# CKR_BM_v4_2_TR.net
KiCad netlist of a schematic drawn in EAGLE
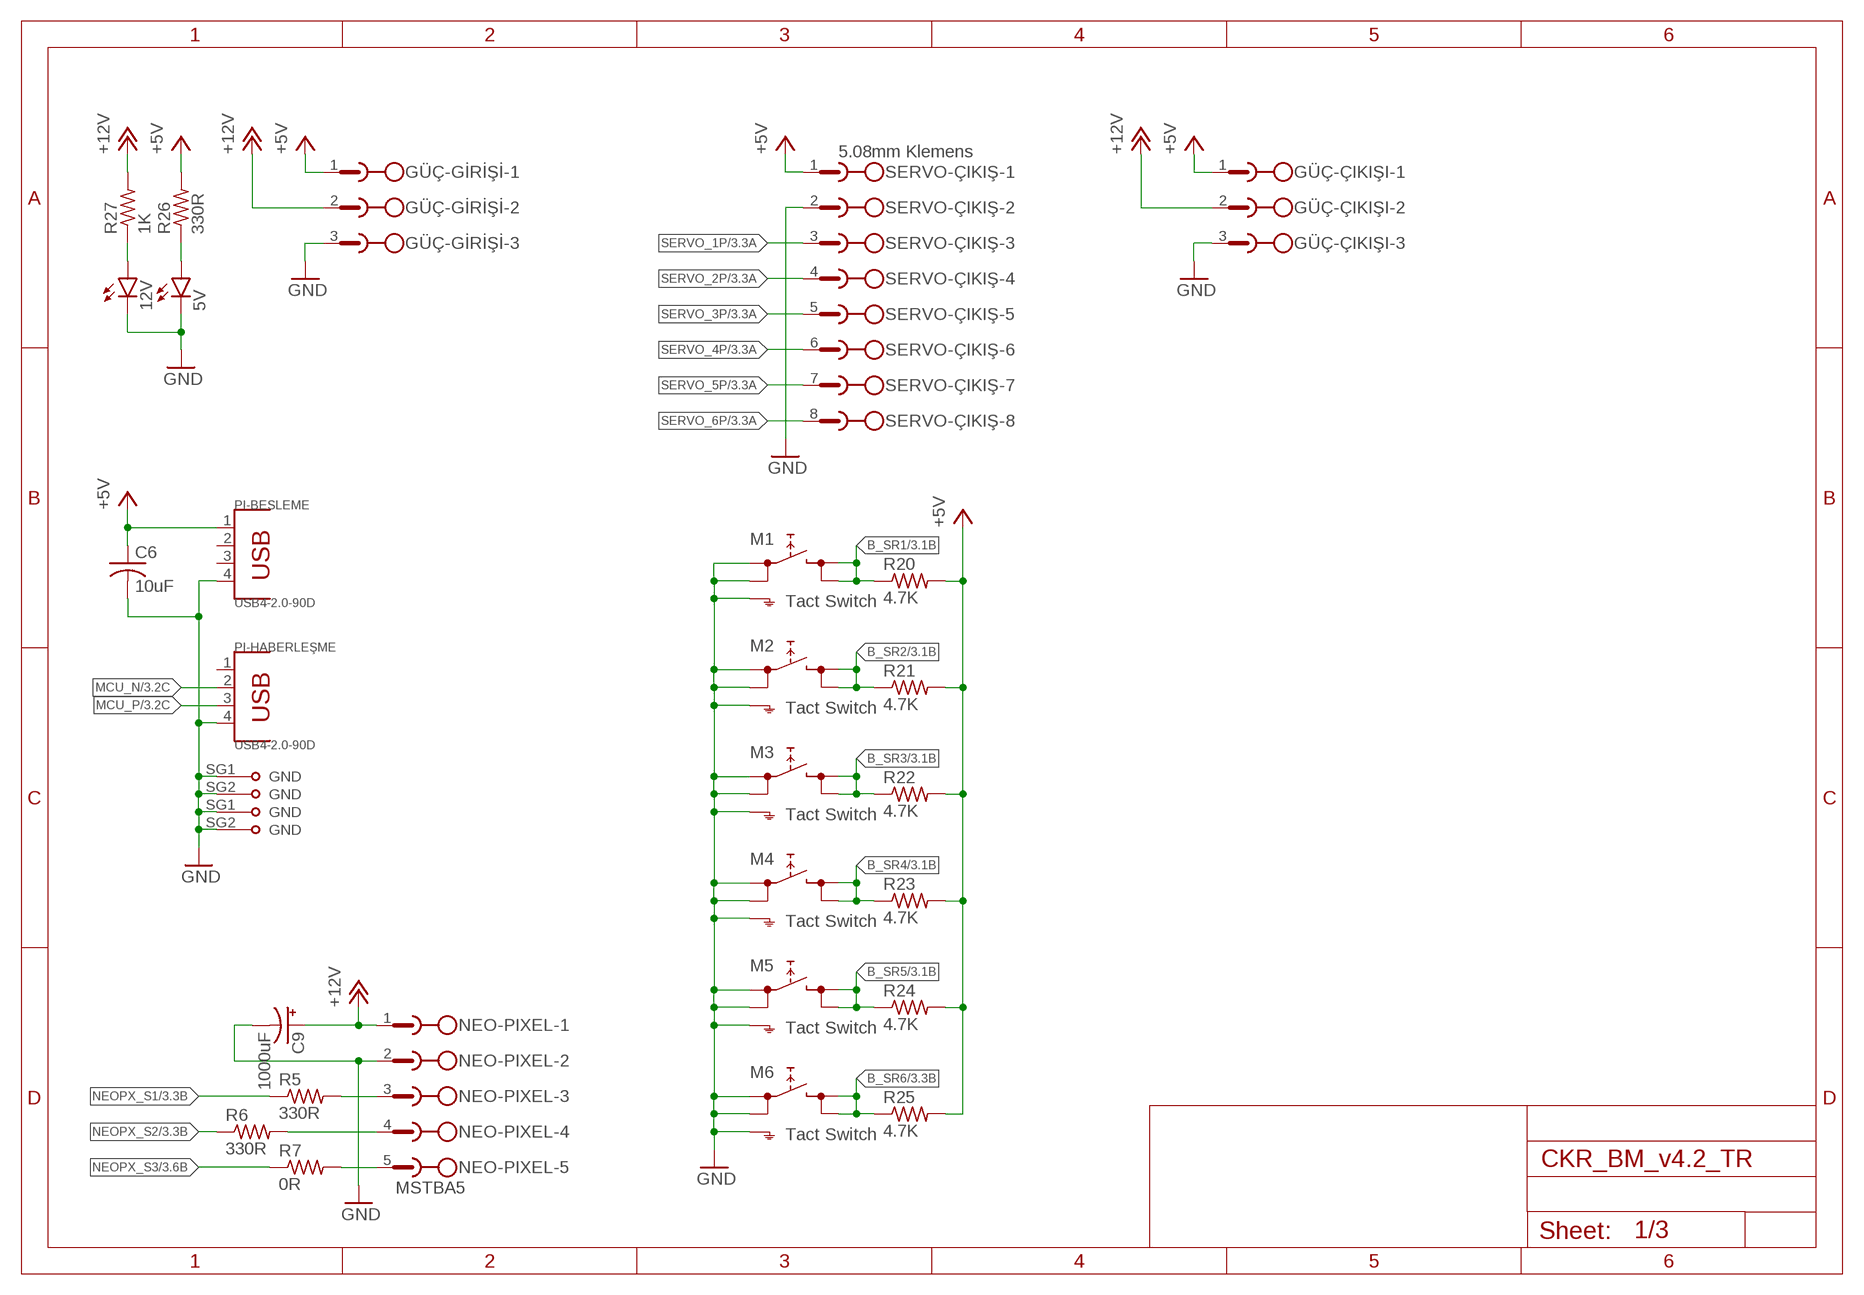
[diagram p0: schematic, sheet 1]
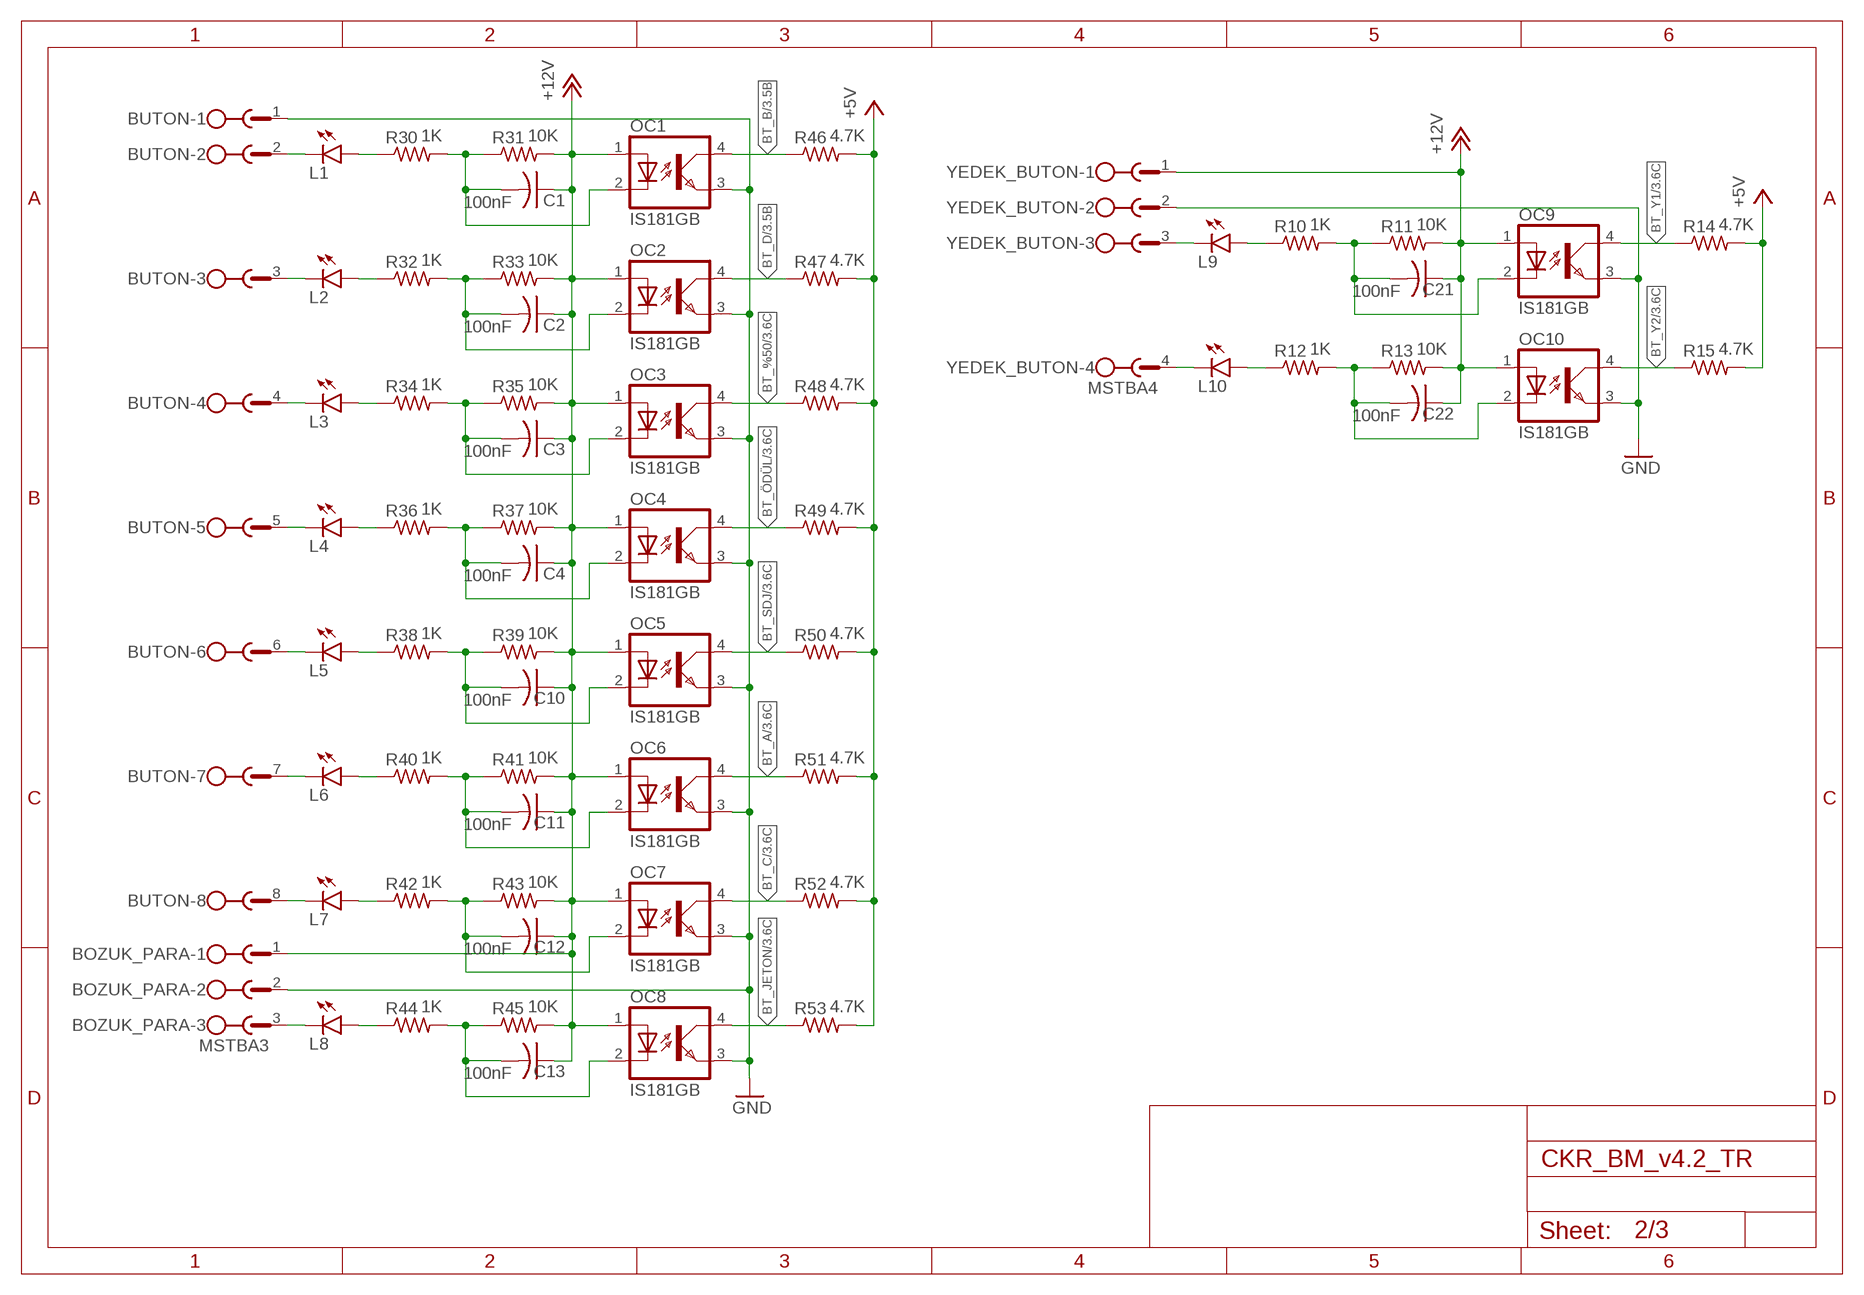
[diagram p1: schematic, sheet 2]
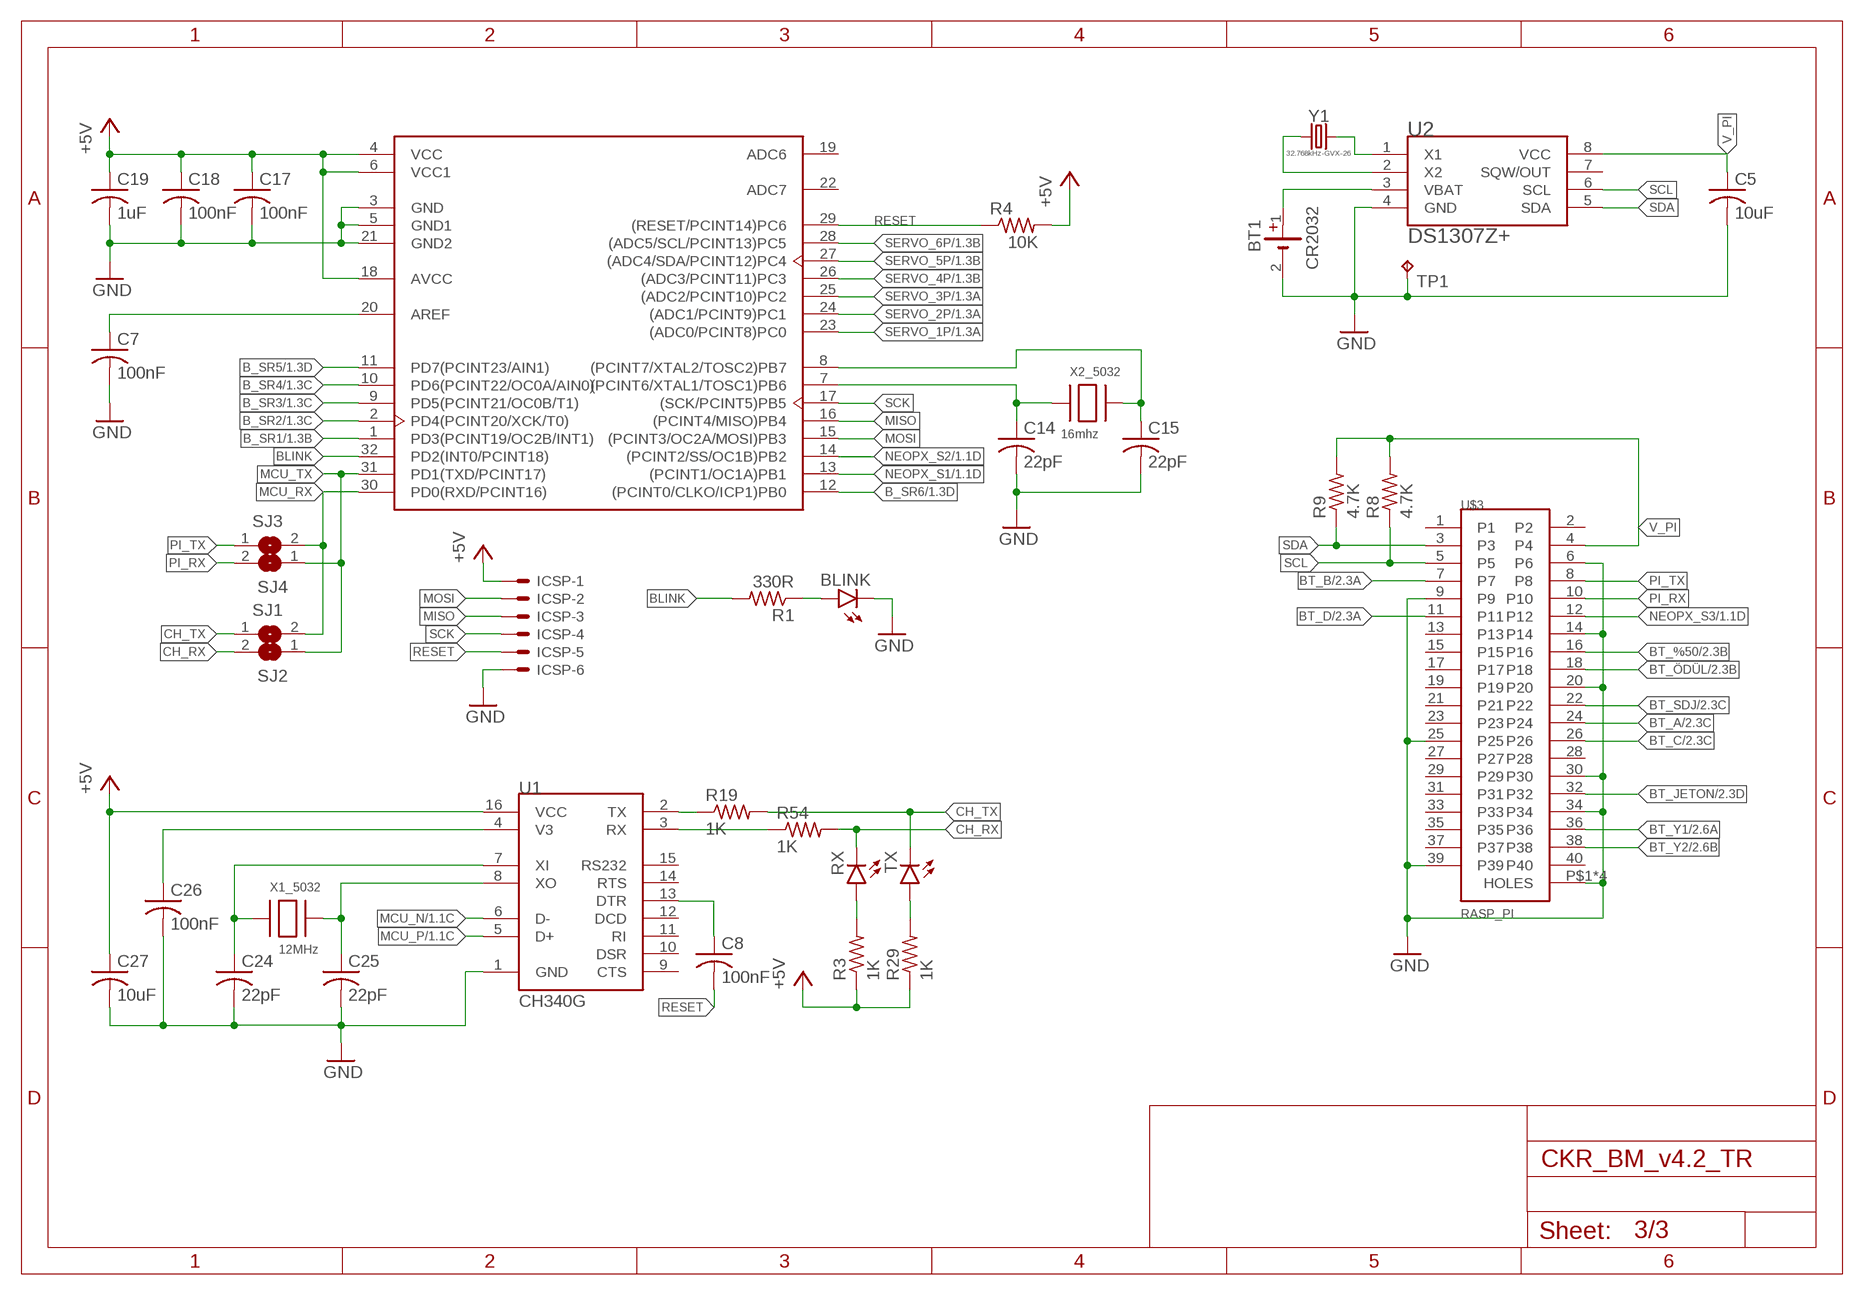
[diagram p2: schematic, sheet 3]

(export (version "E")
  (design (tool "Eeschema 10.0.6"))
  (components
    (comp (ref "BLINK")
      (value "LEDCHIP-LED0805")
      (footprint "eagle-import:CHIP-LED0805")
      (libsource (lib "eagle-import") (part "LEDCHIP-LED0805"))
    )
    (comp (ref "BT1")
      (value "CR2032")
      (footprint "eagle-import:79528211")
      (fields
        (field (name "DIGIKEY_PART_NO") "732-12326-ND")
        (field (name "MANUFACTURER") "Wurth Electronics Inc.")
        (field (name "MPN") "79528211")
        (field (name "CREATED_BY") "PCBLayout.com")
      )
      (libsource (lib "eagle-import") (part "79528211"))
    )
    (comp (ref "C5")
      (value "10uF")
      (footprint "eagle-import:C0805")
      (libsource (lib "eagle-import") (part "C-USC0805"))
    )
    (comp (ref "C7")
      (value "100nF")
      (footprint "eagle-import:C0805")
      (libsource (lib "eagle-import") (part "C-USC0805"))
    )
    (comp (ref "C8")
      (value "100nF")
      (footprint "eagle-import:C0805")
      (libsource (lib "eagle-import") (part "C-USC0805"))
    )
    (comp (ref "C14")
      (value "22pF")
      (footprint "eagle-import:C0805")
      (libsource (lib "eagle-import") (part "C-USC0805"))
    )
    (comp (ref "C15")
      (value "22pF")
      (footprint "eagle-import:C0805")
      (libsource (lib "eagle-import") (part "C-USC0805"))
    )
    (comp (ref "C17")
      (value "100nF")
      (footprint "eagle-import:C0805")
      (libsource (lib "eagle-import") (part "C-USC0805"))
    )
    (comp (ref "C18")
      (value "100nF")
      (footprint "eagle-import:C0805")
      (libsource (lib "eagle-import") (part "C-USC0805"))
    )
    (comp (ref "C19")
      (value "1uF")
      (footprint "eagle-import:C0805")
      (libsource (lib "eagle-import") (part "C-USC0805"))
    )
    (comp (ref "C24")
      (value "22pF")
      (footprint "eagle-import:C0805")
      (libsource (lib "eagle-import") (part "C-USC0805"))
    )
    (comp (ref "C25")
      (value "22pF")
      (footprint "eagle-import:C0805")
      (libsource (lib "eagle-import") (part "C-USC0805"))
    )
    (comp (ref "C26")
      (value "100nF")
      (footprint "eagle-import:C0805")
      (libsource (lib "eagle-import") (part "C-USC0805"))
    )
    (comp (ref "C27")
      (value "10uF")
      (footprint "eagle-import:C0805")
      (libsource (lib "eagle-import") (part "C-USC0805"))
    )
    (comp (ref "ICSP")
      (value "C-GRID-06-70543")
      (footprint "eagle-import:70543-06")
      (fields (field (name "MF") "MOLEX"))
      (libsource (lib "eagle-import") (part "C-GRID-06-70543"))
    )
    (comp (ref "R1")
      (value "330R")
      (footprint "eagle-import:R0805")
      (libsource (lib "eagle-import") (part "R-US_R0805"))
    )
    (comp (ref "R3")
      (value "1K")
      (footprint "eagle-import:R0805")
      (libsource (lib "eagle-import") (part "R-US_R0805"))
    )
    (comp (ref "R4")
      (value "10K")
      (footprint "eagle-import:R0805")
      (libsource (lib "eagle-import") (part "R-US_R0805"))
    )
    (comp (ref "R8")
      (value "4.7K")
      (footprint "eagle-import:R0805")
      (libsource (lib "eagle-import") (part "R-US_R0805"))
    )
    (comp (ref "R9")
      (value "4.7K")
      (footprint "eagle-import:R0805")
      (libsource (lib "eagle-import") (part "R-US_R0805"))
    )
    (comp (ref "R19")
      (value "1K")
      (footprint "eagle-import:R0805")
      (libsource (lib "eagle-import") (part "R-US_R0805"))
    )
    (comp (ref "R29")
      (value "1K")
      (footprint "eagle-import:R0805")
      (libsource (lib "eagle-import") (part "R-US_R0805"))
    )
    (comp (ref "R54")
      (value "1K")
      (footprint "eagle-import:R0805")
      (libsource (lib "eagle-import") (part "R-US_R0805"))
    )
    (comp (ref "RX")
      (value "LEDCHIP-LED0805")
      (footprint "eagle-import:CHIP-LED0805")
      (libsource (lib "eagle-import") (part "LEDCHIP-LED0805"))
    )
    (comp (ref "SJ1") (value "SJ") (footprint "eagle-import:SJ") (libsource (lib "eagle-import") (part "SJ")))
    (comp (ref "SJ2") (value "SJ") (footprint "eagle-import:SJ") (libsource (lib "eagle-import") (part "SJ")))
    (comp (ref "SJ3") (value "SJ") (footprint "eagle-import:SJ") (libsource (lib "eagle-import") (part "SJ")))
    (comp (ref "SJ4") (value "SJ") (footprint "eagle-import:SJ") (libsource (lib "eagle-import") (part "SJ")))
    (comp (ref "TP1")
      (value "GND")
      (footprint "eagle-import:TP15R")
      (libsource (lib "eagle-import") (part "TPTP15R"))
    )
    (comp (ref "TX")
      (value "LEDCHIP-LED0805")
      (footprint "eagle-import:CHIP-LED0805")
      (libsource (lib "eagle-import") (part "LEDCHIP-LED0805"))
    )
    (comp (ref "U$3")
      (value "RASP_PI")
      (footprint "eagle-import:RASP_PI")
      (libsource (lib "eagle-import") (part "RASP_PI"))
    )
    (comp (ref "U1")
      (value "CH340G")
      (footprint "eagle-import:SOIC16")
      (libsource (lib "eagle-import") (part "CH340G"))
    )
    (comp (ref "U2")
      (value "DS1307Z+")
      (footprint "eagle-import:SOIC-8N")
      (fields
        (field (name "DIGI-KEY_PART_NUMBER") "DS1307Z+-ND")
        (field (name "MANUFACTURER") "Maxim Integrated")
        (field (name "CREATED_BY") "PCBLayout.com")
      )
      (libsource (lib "eagle-import") (part "DS1307Z+"))
    )
    (comp (ref "U4")
      (value "ATMEGA328P-AU")
      (footprint "eagle-import:TQFP-32")
      (fields
        (field (name "DIGIKEY_PART_NUMBER") "ATMEGA328P-AU-ND")
        (field (name "MANUFACTURER") "Microchip Technology")
        (field (name "CREATED_BY") "PCBLayout.com")
      )
      (libsource (lib "eagle-import") (part "ATMEGA328P-AU"))
    )
    (comp (ref "X1_5032")
      (value "12MHz")
      (footprint "eagle-import:NX5032")
      (libsource (lib "eagle-import") (part "XTALNX5032"))
    )
    (comp (ref "X2_5032")
      (value "16mhz")
      (footprint "eagle-import:NX5032")
      (libsource (lib "eagle-import") (part "XTALNX5032"))
    )
    (comp (ref "Y1")
      (value "32.768kHz-GVX-26")
      (footprint "eagle-import:CRYSTAL-PTH-2X6-CYL")
      (libsource (lib "eagle-import") (part "CRYSTAL-32.768KHZPTH-2X6"))
    )
    (comp (ref "BOZUK_PARA")
      (value "MSTBA3")
      (footprint "eagle-import:MSTBA3")
      (fields (field (name "MF") "FARNELL") (field (name "MPN") "1757255"))
      (libsource (lib "eagle-import") (part "MSTBA3"))
    )
    (comp (ref "BUTON")
      (value "MSTBA8")
      (footprint "eagle-import:MSTBA8")
      (fields (field (name "MF") "FARNELL") (field (name "MPN") "1757307"))
      (libsource (lib "eagle-import") (part "MSTBA8"))
    )
    (comp (ref "C1")
      (value "100nF")
      (footprint "eagle-import:C0805")
      (libsource (lib "eagle-import") (part "C-USC0805"))
    )
    (comp (ref "C2")
      (value "100nF")
      (footprint "eagle-import:C0805")
      (libsource (lib "eagle-import") (part "C-USC0805"))
    )
    (comp (ref "C3")
      (value "100nF")
      (footprint "eagle-import:C0805")
      (libsource (lib "eagle-import") (part "C-USC0805"))
    )
    (comp (ref "C4")
      (value "100nF")
      (footprint "eagle-import:C0805")
      (libsource (lib "eagle-import") (part "C-USC0805"))
    )
    (comp (ref "C10")
      (value "100nF")
      (footprint "eagle-import:C0805")
      (libsource (lib "eagle-import") (part "C-USC0805"))
    )
    (comp (ref "C11")
      (value "100nF")
      (footprint "eagle-import:C0805")
      (libsource (lib "eagle-import") (part "C-USC0805"))
    )
    (comp (ref "C12")
      (value "100nF")
      (footprint "eagle-import:C0805")
      (libsource (lib "eagle-import") (part "C-USC0805"))
    )
    (comp (ref "C13")
      (value "100nF")
      (footprint "eagle-import:C0805")
      (libsource (lib "eagle-import") (part "C-USC0805"))
    )
    (comp (ref "C21")
      (value "100nF")
      (footprint "eagle-import:C0805")
      (libsource (lib "eagle-import") (part "C-USC0805"))
    )
    (comp (ref "C22")
      (value "100nF")
      (footprint "eagle-import:C0805")
      (libsource (lib "eagle-import") (part "C-USC0805"))
    )
    (comp (ref "L1")
      (value "LEDCHIP-LED0805")
      (footprint "eagle-import:CHIP-LED0805")
      (libsource (lib "eagle-import") (part "LEDCHIP-LED0805"))
    )
    (comp (ref "L2")
      (value "LEDCHIP-LED0805")
      (footprint "eagle-import:CHIP-LED0805")
      (libsource (lib "eagle-import") (part "LEDCHIP-LED0805"))
    )
    (comp (ref "L3")
      (value "LEDCHIP-LED0805")
      (footprint "eagle-import:CHIP-LED0805")
      (libsource (lib "eagle-import") (part "LEDCHIP-LED0805"))
    )
    (comp (ref "L4")
      (value "LEDCHIP-LED0805")
      (footprint "eagle-import:CHIP-LED0805")
      (libsource (lib "eagle-import") (part "LEDCHIP-LED0805"))
    )
    (comp (ref "L5")
      (value "LEDCHIP-LED0805")
      (footprint "eagle-import:CHIP-LED0805")
      (libsource (lib "eagle-import") (part "LEDCHIP-LED0805"))
    )
    (comp (ref "L6")
      (value "LEDCHIP-LED0805")
      (footprint "eagle-import:CHIP-LED0805")
      (libsource (lib "eagle-import") (part "LEDCHIP-LED0805"))
    )
    (comp (ref "L7")
      (value "LEDCHIP-LED0805")
      (footprint "eagle-import:CHIP-LED0805")
      (libsource (lib "eagle-import") (part "LEDCHIP-LED0805"))
    )
    (comp (ref "L8")
      (value "LEDCHIP-LED0805")
      (footprint "eagle-import:CHIP-LED0805")
      (libsource (lib "eagle-import") (part "LEDCHIP-LED0805"))
    )
    (comp (ref "L9")
      (value "LEDCHIP-LED0805")
      (footprint "eagle-import:CHIP-LED0805")
      (libsource (lib "eagle-import") (part "LEDCHIP-LED0805"))
    )
    (comp (ref "L10")
      (value "LEDCHIP-LED0805")
      (footprint "eagle-import:CHIP-LED0805")
      (libsource (lib "eagle-import") (part "LEDCHIP-LED0805"))
    )
    (comp (ref "OC1")
      (value "IS181GB")
      (footprint "eagle-import:SO-4")
      (libsource (lib "eagle-import") (part "TLP181"))
    )
    (comp (ref "OC2")
      (value "IS181GB")
      (footprint "eagle-import:SO-4")
      (libsource (lib "eagle-import") (part "TLP181"))
    )
    (comp (ref "OC3")
      (value "IS181GB")
      (footprint "eagle-import:SO-4")
      (libsource (lib "eagle-import") (part "TLP181"))
    )
    (comp (ref "OC4")
      (value "IS181GB")
      (footprint "eagle-import:SO-4")
      (libsource (lib "eagle-import") (part "TLP181"))
    )
    (comp (ref "OC5")
      (value "IS181GB")
      (footprint "eagle-import:SO-4")
      (libsource (lib "eagle-import") (part "TLP181"))
    )
    (comp (ref "OC6")
      (value "IS181GB")
      (footprint "eagle-import:SO-4")
      (libsource (lib "eagle-import") (part "TLP181"))
    )
    (comp (ref "OC7")
      (value "IS181GB")
      (footprint "eagle-import:SO-4")
      (libsource (lib "eagle-import") (part "TLP181"))
    )
    (comp (ref "OC8")
      (value "IS181GB")
      (footprint "eagle-import:SO-4")
      (libsource (lib "eagle-import") (part "TLP181"))
    )
    (comp (ref "OC9")
      (value "IS181GB")
      (footprint "eagle-import:SO-4")
      (libsource (lib "eagle-import") (part "TLP181"))
    )
    (comp (ref "OC10")
      (value "IS181GB")
      (footprint "eagle-import:SO-4")
      (libsource (lib "eagle-import") (part "TLP181"))
    )
    (comp (ref "R10")
      (value "1K")
      (footprint "eagle-import:R0805")
      (libsource (lib "eagle-import") (part "R-US_R0805"))
    )
    (comp (ref "R11")
      (value "10K")
      (footprint "eagle-import:R0805")
      (libsource (lib "eagle-import") (part "R-US_R0805"))
    )
    (comp (ref "R12")
      (value "1K")
      (footprint "eagle-import:R0805")
      (libsource (lib "eagle-import") (part "R-US_R0805"))
    )
    (comp (ref "R13")
      (value "10K")
      (footprint "eagle-import:R0805")
      (libsource (lib "eagle-import") (part "R-US_R0805"))
    )
    (comp (ref "R14")
      (value "4.7K")
      (footprint "eagle-import:R0805")
      (libsource (lib "eagle-import") (part "R-US_R0805"))
    )
    (comp (ref "R15")
      (value "4.7K")
      (footprint "eagle-import:R0805")
      (libsource (lib "eagle-import") (part "R-US_R0805"))
    )
    (comp (ref "R30")
      (value "1K")
      (footprint "eagle-import:R0805")
      (libsource (lib "eagle-import") (part "R-US_R0805"))
    )
    (comp (ref "R31")
      (value "10K")
      (footprint "eagle-import:R0805")
      (libsource (lib "eagle-import") (part "R-US_R0805"))
    )
    (comp (ref "R32")
      (value "1K")
      (footprint "eagle-import:R0805")
      (libsource (lib "eagle-import") (part "R-US_R0805"))
    )
    (comp (ref "R33")
      (value "10K")
      (footprint "eagle-import:R0805")
      (libsource (lib "eagle-import") (part "R-US_R0805"))
    )
    (comp (ref "R34")
      (value "1K")
      (footprint "eagle-import:R0805")
      (libsource (lib "eagle-import") (part "R-US_R0805"))
    )
    (comp (ref "R35")
      (value "10K")
      (footprint "eagle-import:R0805")
      (libsource (lib "eagle-import") (part "R-US_R0805"))
    )
    (comp (ref "R36")
      (value "1K")
      (footprint "eagle-import:R0805")
      (libsource (lib "eagle-import") (part "R-US_R0805"))
    )
    (comp (ref "R37")
      (value "10K")
      (footprint "eagle-import:R0805")
      (libsource (lib "eagle-import") (part "R-US_R0805"))
    )
    (comp (ref "R38")
      (value "1K")
      (footprint "eagle-import:R0805")
      (libsource (lib "eagle-import") (part "R-US_R0805"))
    )
    (comp (ref "R39")
      (value "10K")
      (footprint "eagle-import:R0805")
      (libsource (lib "eagle-import") (part "R-US_R0805"))
    )
    (comp (ref "R40")
      (value "1K")
      (footprint "eagle-import:R0805")
      (libsource (lib "eagle-import") (part "R-US_R0805"))
    )
    (comp (ref "R41")
      (value "10K")
      (footprint "eagle-import:R0805")
      (libsource (lib "eagle-import") (part "R-US_R0805"))
    )
    (comp (ref "R42")
      (value "1K")
      (footprint "eagle-import:R0805")
      (libsource (lib "eagle-import") (part "R-US_R0805"))
    )
    (comp (ref "R43")
      (value "10K")
      (footprint "eagle-import:R0805")
      (libsource (lib "eagle-import") (part "R-US_R0805"))
    )
    (comp (ref "R44")
      (value "1K")
      (footprint "eagle-import:R0805")
      (libsource (lib "eagle-import") (part "R-US_R0805"))
    )
    (comp (ref "R45")
      (value "10K")
      (footprint "eagle-import:R0805")
      (libsource (lib "eagle-import") (part "R-US_R0805"))
    )
    (comp (ref "R46")
      (value "4.7K")
      (footprint "eagle-import:R0805")
      (libsource (lib "eagle-import") (part "R-US_R0805"))
    )
    (comp (ref "R47")
      (value "4.7K")
      (footprint "eagle-import:R0805")
      (libsource (lib "eagle-import") (part "R-US_R0805"))
    )
    (comp (ref "R48")
      (value "4.7K")
      (footprint "eagle-import:R0805")
      (libsource (lib "eagle-import") (part "R-US_R0805"))
    )
    (comp (ref "R49")
      (value "4.7K")
      (footprint "eagle-import:R0805")
      (libsource (lib "eagle-import") (part "R-US_R0805"))
    )
    (comp (ref "R50")
      (value "4.7K")
      (footprint "eagle-import:R0805")
      (libsource (lib "eagle-import") (part "R-US_R0805"))
    )
    (comp (ref "R51")
      (value "4.7K")
      (footprint "eagle-import:R0805")
      (libsource (lib "eagle-import") (part "R-US_R0805"))
    )
    (comp (ref "R52")
      (value "4.7K")
      (footprint "eagle-import:R0805")
      (libsource (lib "eagle-import") (part "R-US_R0805"))
    )
    (comp (ref "R53")
      (value "4.7K")
      (footprint "eagle-import:R0805")
      (libsource (lib "eagle-import") (part "R-US_R0805"))
    )
    (comp (ref "YEDEK_BUTON")
      (value "MSTBA4")
      (footprint "eagle-import:MSTBA4")
      (fields (field (name "MF") "FARNELL") (field (name "MPN") "1757268"))
      (libsource (lib "eagle-import") (part "MSTBA4"))
    )
    (comp (ref "5V")
      (value "LEDCHIP-LED0805")
      (footprint "eagle-import:CHIP-LED0805")
      (libsource (lib "eagle-import") (part "LEDCHIP-LED0805"))
    )
    (comp (ref "12V")
      (value "LEDCHIP-LED0805")
      (footprint "eagle-import:CHIP-LED0805")
      (libsource (lib "eagle-import") (part "LEDCHIP-LED0805"))
    )
    (comp (ref "C6")
      (value "10uF")
      (footprint "eagle-import:C0805")
      (libsource (lib "eagle-import") (part "C-USC0805"))
    )
    (comp (ref "C9")
      (value "1000uF")
      (footprint "eagle-import:140CLH-1010")
      (libsource (lib "eagle-import") (part "CPOL-US140CLH-1010"))
    )
    (comp (ref "GÜÇ-GİRİŞİ")
      (value "5.08mm Klemens")
      (footprint "eagle-import:MSTBA3")
      (fields (field (name "MF") "FARNELL") (field (name "MPN") "1757255"))
      (libsource (lib "eagle-import") (part "MSTBA3"))
    )
    (comp (ref "GÜÇ-ÇIKIŞI")
      (value "5.08mm Klemens")
      (footprint "eagle-import:MSTBA3")
      (fields (field (name "MF") "FARNELL") (field (name "MPN") "1757255"))
      (libsource (lib "eagle-import") (part "MSTBA3"))
    )
    (comp (ref "M1")
      (value "Tact Switch")
      (footprint "eagle-import:SKHMPXE010")
      (libsource (lib "eagle-import") (part "SKHMPE010S"))
    )
    (comp (ref "M2")
      (value "Tact Switch")
      (footprint "eagle-import:SKHMPXE010")
      (libsource (lib "eagle-import") (part "SKHMPE010S"))
    )
    (comp (ref "M3")
      (value "Tact Switch")
      (footprint "eagle-import:SKHMPXE010")
      (libsource (lib "eagle-import") (part "SKHMPE010S"))
    )
    (comp (ref "M4")
      (value "Tact Switch")
      (footprint "eagle-import:SKHMPXE010")
      (libsource (lib "eagle-import") (part "SKHMPE010S"))
    )
    (comp (ref "M5")
      (value "Tact Switch")
      (footprint "eagle-import:SKHMPXE010")
      (libsource (lib "eagle-import") (part "SKHMPE010S"))
    )
    (comp (ref "M6")
      (value "Tact Switch")
      (footprint "eagle-import:SKHMPXE010")
      (libsource (lib "eagle-import") (part "SKHMPE010S"))
    )
    (comp (ref "NEO-PIXEL")
      (value "MSTBA5")
      (footprint "eagle-import:MSTBA5")
      (fields (field (name "MPN") "1757271"))
      (libsource (lib "eagle-import") (part "MSTBA5"))
    )
    (comp (ref "PI-BESLEME")
      (value "USB4-2.0-90D")
      (footprint "eagle-import:USB4+2P-2.0-90D")
      (libsource (lib "eagle-import") (part "DIP-USB-A-TYPE-FMAL(4+2P-2.0-90D)"))
    )
    (comp (ref "PI-HABERLEŞME")
      (value "USB4-2.0-90D")
      (footprint "eagle-import:USB4+2P-2.0-90D")
      (libsource (lib "eagle-import") (part "DIP-USB-A-TYPE-FMAL(4+2P-2.0-90D)"))
    )
    (comp (ref "R5")
      (value "330R")
      (footprint "eagle-import:R0805")
      (libsource (lib "eagle-import") (part "R-US_R0805"))
    )
    (comp (ref "R6")
      (value "330R")
      (footprint "eagle-import:R0805")
      (libsource (lib "eagle-import") (part "R-US_R0805"))
    )
    (comp (ref "R7")
      (value "0R")
      (footprint "eagle-import:R0805")
      (libsource (lib "eagle-import") (part "R-US_R0805"))
    )
    (comp (ref "R20")
      (value "4.7K")
      (footprint "eagle-import:R0805")
      (libsource (lib "eagle-import") (part "R-US_R0805"))
    )
    (comp (ref "R21")
      (value "4.7K")
      (footprint "eagle-import:R0805")
      (libsource (lib "eagle-import") (part "R-US_R0805"))
    )
    (comp (ref "R22")
      (value "4.7K")
      (footprint "eagle-import:R0805")
      (libsource (lib "eagle-import") (part "R-US_R0805"))
    )
    (comp (ref "R23")
      (value "4.7K")
      (footprint "eagle-import:R0805")
      (libsource (lib "eagle-import") (part "R-US_R0805"))
    )
    (comp (ref "R24")
      (value "4.7K")
      (footprint "eagle-import:R0805")
      (libsource (lib "eagle-import") (part "R-US_R0805"))
    )
    (comp (ref "R25")
      (value "4.7K")
      (footprint "eagle-import:R0805")
      (libsource (lib "eagle-import") (part "R-US_R0805"))
    )
    (comp (ref "R26")
      (value "330R")
      (footprint "eagle-import:R0805")
      (libsource (lib "eagle-import") (part "R-US_R0805"))
    )
    (comp (ref "R27")
      (value "1K")
      (footprint "eagle-import:R0805")
      (libsource (lib "eagle-import") (part "R-US_R0805"))
    )
    (comp (ref "SERVO-ÇIKIŞ")
      (value "5.08mm Klemens")
      (footprint "eagle-import:MSTBA8")
      (fields (field (name "MF") "FARNELL") (field (name "MPN") "1757307"))
      (libsource (lib "eagle-import") (part "MSTBA8"))
    )
  )
  (nets
    (net (code "1") (name "+5V") (class "Default")
      (node (ref "C17") (pin "1") (pinfunction "1_1") (pintype "passive"))
      (node (ref "C18") (pin "1") (pinfunction "1_1") (pintype "passive"))
      (node (ref "C19") (pin "1") (pinfunction "1_1") (pintype "passive"))
      (node (ref "C27") (pin "1") (pinfunction "1_1") (pintype "passive"))
      (node (ref "C6") (pin "1") (pinfunction "1_1") (pintype "passive"))
      (node (ref "GÜÇ-GİRİŞİ") (pin "1") (pinfunction "1_1") (pintype "passive"))
      (node (ref "GÜÇ-ÇIKIŞI") (pin "1") (pinfunction "1_1") (pintype "passive"))
      (node (ref "ICSP") (pin "1") (pinfunction "S_1") (pintype "passive"))
      (node (ref "PI-BESLEME") (pin "1") (pinfunction "1_1") (pintype "bidirectional"))
      (node (ref "R14") (pin "2") (pinfunction "2_2") (pintype "passive"))
      (node (ref "R15") (pin "2") (pinfunction "2_2") (pintype "passive"))
      (node (ref "R20") (pin "2") (pinfunction "2_2") (pintype "passive"))
      (node (ref "R21") (pin "2") (pinfunction "2_2") (pintype "passive"))
      (node (ref "R22") (pin "2") (pinfunction "2_2") (pintype "passive"))
      (node (ref "R23") (pin "2") (pinfunction "2_2") (pintype "passive"))
      (node (ref "R24") (pin "2") (pinfunction "2_2") (pintype "passive"))
      (node (ref "R25") (pin "2") (pinfunction "2_2") (pintype "passive"))
      (node (ref "R26") (pin "2") (pinfunction "2_2") (pintype "passive"))
      (node (ref "R29") (pin "1") (pinfunction "1_1") (pintype "passive"))
      (node (ref "R3") (pin "1") (pinfunction "1_1") (pintype "passive"))
      (node (ref "R4") (pin "2") (pinfunction "2_2") (pintype "passive"))
      (node (ref "R46") (pin "2") (pinfunction "2_2") (pintype "passive"))
      (node (ref "R47") (pin "2") (pinfunction "2_2") (pintype "passive"))
      (node (ref "R48") (pin "2") (pinfunction "2_2") (pintype "passive"))
      (node (ref "R49") (pin "2") (pinfunction "2_2") (pintype "passive"))
      (node (ref "R50") (pin "2") (pinfunction "2_2") (pintype "passive"))
      (node (ref "R51") (pin "2") (pinfunction "2_2") (pintype "passive"))
      (node (ref "R52") (pin "2") (pinfunction "2_2") (pintype "passive"))
      (node (ref "R53") (pin "2") (pinfunction "2_2") (pintype "passive"))
      (node (ref "SERVO-ÇIKIŞ") (pin "1") (pinfunction "1_1") (pintype "passive"))
      (node (ref "U1") (pin "16") (pinfunction "VCC_16") (pintype "bidirectional"))
      (node (ref "U4") (pin "18") (pinfunction "AVCC_18") (pintype "power_in"))
      (node (ref "U4") (pin "4") (pinfunction "VCC_4") (pintype "power_in"))
      (node (ref "U4") (pin "6") (pinfunction "VCC1_6") (pintype "power_in"))
    )
    (net (code "2") (name "+12V") (class "Default")
      (node (ref "BOZUK_PARA") (pin "1") (pinfunction "1_1") (pintype "passive"))
      (node (ref "C1") (pin "1") (pinfunction "1_1") (pintype "passive"))
      (node (ref "C10") (pin "1") (pinfunction "1_1") (pintype "passive"))
      (node (ref "C11") (pin "1") (pinfunction "1_1") (pintype "passive"))
      (node (ref "C12") (pin "1") (pinfunction "1_1") (pintype "passive"))
      (node (ref "C13") (pin "1") (pinfunction "1_1") (pintype "passive"))
      (node (ref "C2") (pin "1") (pinfunction "1_1") (pintype "passive"))
      (node (ref "C21") (pin "1") (pinfunction "1_1") (pintype "passive"))
      (node (ref "C22") (pin "1") (pinfunction "1_1") (pintype "passive"))
      (node (ref "C3") (pin "1") (pinfunction "1_1") (pintype "passive"))
      (node (ref "C4") (pin "1") (pinfunction "1_1") (pintype "passive"))
      (node (ref "C9") (pin "+") (pinfunction "+_+") (pintype "passive"))
      (node (ref "GÜÇ-GİRİŞİ") (pin "2") (pinfunction "1_2") (pintype "passive"))
      (node (ref "GÜÇ-ÇIKIŞI") (pin "2") (pinfunction "1_2") (pintype "passive"))
      (node (ref "NEO-PIXEL") (pin "1") (pinfunction "1_1") (pintype "passive"))
      (node (ref "OC1") (pin "1") (pinfunction "A_1") (pintype "passive"))
      (node (ref "OC10") (pin "1") (pinfunction "A_1") (pintype "passive"))
      (node (ref "OC2") (pin "1") (pinfunction "A_1") (pintype "passive"))
      (node (ref "OC3") (pin "1") (pinfunction "A_1") (pintype "passive"))
      (node (ref "OC4") (pin "1") (pinfunction "A_1") (pintype "passive"))
      (node (ref "OC5") (pin "1") (pinfunction "A_1") (pintype "passive"))
      (node (ref "OC6") (pin "1") (pinfunction "A_1") (pintype "passive"))
      (node (ref "OC7") (pin "1") (pinfunction "A_1") (pintype "passive"))
      (node (ref "OC8") (pin "1") (pinfunction "A_1") (pintype "passive"))
      (node (ref "OC9") (pin "1") (pinfunction "A_1") (pintype "passive"))
      (node (ref "R11") (pin "2") (pinfunction "2_2") (pintype "passive"))
      (node (ref "R13") (pin "2") (pinfunction "2_2") (pintype "passive"))
      (node (ref "R27") (pin "2") (pinfunction "2_2") (pintype "passive"))
      (node (ref "R31") (pin "2") (pinfunction "2_2") (pintype "passive"))
      (node (ref "R33") (pin "2") (pinfunction "2_2") (pintype "passive"))
      (node (ref "R35") (pin "2") (pinfunction "2_2") (pintype "passive"))
      (node (ref "R37") (pin "2") (pinfunction "2_2") (pintype "passive"))
      (node (ref "R39") (pin "2") (pinfunction "2_2") (pintype "passive"))
      (node (ref "R41") (pin "2") (pinfunction "2_2") (pintype "passive"))
      (node (ref "R43") (pin "2") (pinfunction "2_2") (pintype "passive"))
      (node (ref "R45") (pin "2") (pinfunction "2_2") (pintype "passive"))
      (node (ref "YEDEK_BUTON") (pin "1") (pinfunction "1_1") (pintype "passive"))
    )
    (net (code "3") (name "BLINK") (class "Default")
      (node (ref "R1") (pin "2") (pinfunction "2_2") (pintype "passive"))
      (node (ref "U4") (pin "32") (pinfunction "PD2(INT0/PCINT18)_32") (pintype "bidirectional"))
    )
    (net (code "4") (name "BT_%50") (class "Default")
      (node (ref "OC3") (pin "4") (pinfunction "COL_4") (pintype "passive"))
      (node (ref "R48") (pin "1") (pinfunction "1_1") (pintype "passive"))
      (node (ref "U$3") (pin "16") (pinfunction "P16_16") (pintype "bidirectional"))
    )
    (net (code "5") (name "BT_A") (class "Default")
      (node (ref "OC6") (pin "4") (pinfunction "COL_4") (pintype "passive"))
      (node (ref "R51") (pin "1") (pinfunction "1_1") (pintype "passive"))
      (node (ref "U$3") (pin "24") (pinfunction "P24_24") (pintype "bidirectional"))
    )
    (net (code "6") (name "BT_B") (class "Default")
      (node (ref "OC1") (pin "4") (pinfunction "COL_4") (pintype "passive"))
      (node (ref "R46") (pin "1") (pinfunction "1_1") (pintype "passive"))
      (node (ref "U$3") (pin "7") (pinfunction "P7_7") (pintype "bidirectional"))
    )
    (net (code "7") (name "BT_C") (class "Default")
      (node (ref "OC7") (pin "4") (pinfunction "COL_4") (pintype "passive"))
      (node (ref "R52") (pin "1") (pinfunction "1_1") (pintype "passive"))
      (node (ref "U$3") (pin "26") (pinfunction "P26_26") (pintype "bidirectional"))
    )
    (net (code "8") (name "BT_D") (class "Default")
      (node (ref "OC2") (pin "4") (pinfunction "COL_4") (pintype "passive"))
      (node (ref "R47") (pin "1") (pinfunction "1_1") (pintype "passive"))
      (node (ref "U$3") (pin "11") (pinfunction "P11_11") (pintype "bidirectional"))
    )
    (net (code "9") (name "BT_JETON") (class "Default")
      (node (ref "OC8") (pin "4") (pinfunction "COL_4") (pintype "passive"))
      (node (ref "R53") (pin "1") (pinfunction "1_1") (pintype "passive"))
      (node (ref "U$3") (pin "32") (pinfunction "P32_32") (pintype "bidirectional"))
    )
    (net (code "10") (name "BT_SDJ") (class "Default")
      (node (ref "OC5") (pin "4") (pinfunction "COL_4") (pintype "passive"))
      (node (ref "R50") (pin "1") (pinfunction "1_1") (pintype "passive"))
      (node (ref "U$3") (pin "22") (pinfunction "P22_22") (pintype "bidirectional"))
    )
    (net (code "11") (name "BT_Y1") (class "Default")
      (node (ref "OC9") (pin "4") (pinfunction "COL_4") (pintype "passive"))
      (node (ref "R14") (pin "1") (pinfunction "1_1") (pintype "passive"))
      (node (ref "U$3") (pin "36") (pinfunction "P36_36") (pintype "bidirectional"))
    )
    (net (code "12") (name "BT_Y2") (class "Default")
      (node (ref "OC10") (pin "4") (pinfunction "COL_4") (pintype "passive"))
      (node (ref "R15") (pin "1") (pinfunction "1_1") (pintype "passive"))
      (node (ref "U$3") (pin "38") (pinfunction "P38_38") (pintype "bidirectional"))
    )
    (net (code "13") (name "BT_ÖDÜL") (class "Default")
      (node (ref "OC4") (pin "4") (pinfunction "COL_4") (pintype "passive"))
      (node (ref "R49") (pin "1") (pinfunction "1_1") (pintype "passive"))
      (node (ref "U$3") (pin "18") (pinfunction "P18_18") (pintype "bidirectional"))
    )
    (net (code "14") (name "B_SR1") (class "Default")
      (node (ref "M1") (pin "3") (pinfunction "2.1_3") (pintype "passive"))
      (node (ref "M1") (pin "4") (pinfunction "2.2_4") (pintype "passive"))
      (node (ref "R20") (pin "1") (pinfunction "1_1") (pintype "passive"))
      (node (ref "U4") (pin "1") (pinfunction "PD3(PCINT19/OC2B/INT1)_1") (pintype "bidirectional"))
    )
    (net (code "15") (name "B_SR2") (class "Default")
      (node (ref "M2") (pin "3") (pinfunction "2.1_3") (pintype "passive"))
      (node (ref "M2") (pin "4") (pinfunction "2.2_4") (pintype "passive"))
      (node (ref "R21") (pin "1") (pinfunction "1_1") (pintype "passive"))
      (node (ref "U4") (pin "2") (pinfunction "PD4(PCINT20/XCK/T0)_2") (pintype "bidirectional"))
    )
    (net (code "16") (name "B_SR3") (class "Default")
      (node (ref "M3") (pin "3") (pinfunction "2.1_3") (pintype "passive"))
      (node (ref "M3") (pin "4") (pinfunction "2.2_4") (pintype "passive"))
      (node (ref "R22") (pin "1") (pinfunction "1_1") (pintype "passive"))
      (node (ref "U4") (pin "9") (pinfunction "PD5(PCINT21/OC0B/T1)_9") (pintype "bidirectional"))
    )
    (net (code "17") (name "B_SR4") (class "Default")
      (node (ref "M4") (pin "3") (pinfunction "2.1_3") (pintype "passive"))
      (node (ref "M4") (pin "4") (pinfunction "2.2_4") (pintype "passive"))
      (node (ref "R23") (pin "1") (pinfunction "1_1") (pintype "passive"))
      (node (ref "U4") (pin "10") (pinfunction "PD6(PCINT22/OC0A/AIN0)_10") (pintype "bidirectional"))
    )
    (net (code "18") (name "B_SR5") (class "Default")
      (node (ref "M5") (pin "3") (pinfunction "2.1_3") (pintype "passive"))
      (node (ref "M5") (pin "4") (pinfunction "2.2_4") (pintype "passive"))
      (node (ref "R24") (pin "1") (pinfunction "1_1") (pintype "passive"))
      (node (ref "U4") (pin "11") (pinfunction "PD7(PCINT23/AIN1)_11") (pintype "bidirectional"))
    )
    (net (code "19") (name "B_SR6") (class "Default")
      (node (ref "M6") (pin "3") (pinfunction "2.1_3") (pintype "passive"))
      (node (ref "M6") (pin "4") (pinfunction "2.2_4") (pintype "passive"))
      (node (ref "R25") (pin "1") (pinfunction "1_1") (pintype "passive"))
      (node (ref "U4") (pin "12") (pinfunction "(PCINT0/CLKO/ICP1)PB0_12") (pintype "bidirectional"))
    )
    (net (code "20") (name "CH_RX") (class "Default")
      (node (ref "R54") (pin "2") (pinfunction "2_2") (pintype "passive"))
      (node (ref "RX") (pin "C") (pinfunction "C_C") (pintype "passive"))
      (node (ref "SJ2") (pin "2") (pinfunction "2_2") (pintype "passive"))
    )
    (net (code "21") (name "CH_TX") (class "Default")
      (node (ref "R19") (pin "2") (pinfunction "2_2") (pintype "passive"))
      (node (ref "SJ1") (pin "1") (pinfunction "1_1") (pintype "passive"))
      (node (ref "TX") (pin "C") (pinfunction "C_C") (pintype "passive"))
    )
    (net (code "22") (name "GND") (class "Default")
      (node (ref "12V") (pin "C") (pinfunction "C_C") (pintype "passive"))
      (node (ref "5V") (pin "C") (pinfunction "C_C") (pintype "passive"))
      (node (ref "BLINK") (pin "C") (pinfunction "C_C") (pintype "passive"))
      (node (ref "BOZUK_PARA") (pin "2") (pinfunction "1_2") (pintype "passive"))
      (node (ref "BT1") (pin "2") (pinfunction "-_2") (pintype "passive"))
      (node (ref "BUTON") (pin "1") (pinfunction "1_1") (pintype "passive"))
      (node (ref "C14") (pin "2") (pinfunction "2_2") (pintype "passive"))
      (node (ref "C15") (pin "2") (pinfunction "2_2") (pintype "passive"))
      (node (ref "C17") (pin "2") (pinfunction "2_2") (pintype "passive"))
      (node (ref "C18") (pin "2") (pinfunction "2_2") (pintype "passive"))
      (node (ref "C19") (pin "2") (pinfunction "2_2") (pintype "passive"))
      (node (ref "C24") (pin "2") (pinfunction "2_2") (pintype "passive"))
      (node (ref "C25") (pin "2") (pinfunction "2_2") (pintype "passive"))
      (node (ref "C26") (pin "2") (pinfunction "2_2") (pintype "passive"))
      (node (ref "C27") (pin "2") (pinfunction "2_2") (pintype "passive"))
      (node (ref "C5") (pin "2") (pinfunction "2_2") (pintype "passive"))
      (node (ref "C6") (pin "2") (pinfunction "2_2") (pintype "passive"))
      (node (ref "C7") (pin "2") (pinfunction "2_2") (pintype "passive"))
      (node (ref "C9") (pin "-") (pinfunction "-_-") (pintype "passive"))
      (node (ref "GÜÇ-GİRİŞİ") (pin "3") (pinfunction "1_3") (pintype "passive"))
      (node (ref "GÜÇ-ÇIKIŞI") (pin "3") (pinfunction "1_3") (pintype "passive"))
      (node (ref "ICSP") (pin "6") (pinfunction "S_6") (pintype "passive"))
      (node (ref "M1") (pin "1") (pinfunction "1.1_1") (pintype "passive"))
      (node (ref "M1") (pin "2") (pinfunction "1.2_2") (pintype "passive"))
      (node (ref "M1") (pin "5") (pinfunction "SH_5") (pintype "passive"))
      (node (ref "M2") (pin "1") (pinfunction "1.1_1") (pintype "passive"))
      (node (ref "M2") (pin "2") (pinfunction "1.2_2") (pintype "passive"))
      (node (ref "M2") (pin "5") (pinfunction "SH_5") (pintype "passive"))
      (node (ref "M3") (pin "1") (pinfunction "1.1_1") (pintype "passive"))
      (node (ref "M3") (pin "2") (pinfunction "1.2_2") (pintype "passive"))
      (node (ref "M3") (pin "5") (pinfunction "SH_5") (pintype "passive"))
      (node (ref "M4") (pin "1") (pinfunction "1.1_1") (pintype "passive"))
      (node (ref "M4") (pin "2") (pinfunction "1.2_2") (pintype "passive"))
      (node (ref "M4") (pin "5") (pinfunction "SH_5") (pintype "passive"))
      (node (ref "M5") (pin "1") (pinfunction "1.1_1") (pintype "passive"))
      (node (ref "M5") (pin "2") (pinfunction "1.2_2") (pintype "passive"))
      (node (ref "M5") (pin "5") (pinfunction "SH_5") (pintype "passive"))
      (node (ref "M6") (pin "1") (pinfunction "1.1_1") (pintype "passive"))
      (node (ref "M6") (pin "2") (pinfunction "1.2_2") (pintype "passive"))
      (node (ref "M6") (pin "5") (pinfunction "SH_5") (pintype "passive"))
      (node (ref "NEO-PIXEL") (pin "2") (pinfunction "1_2") (pintype "passive"))
      (node (ref "OC1") (pin "3") (pinfunction "EMIT_3") (pintype "passive"))
      (node (ref "OC10") (pin "3") (pinfunction "EMIT_3") (pintype "passive"))
      (node (ref "OC2") (pin "3") (pinfunction "EMIT_3") (pintype "passive"))
      (node (ref "OC3") (pin "3") (pinfunction "EMIT_3") (pintype "passive"))
      (node (ref "OC4") (pin "3") (pinfunction "EMIT_3") (pintype "passive"))
      (node (ref "OC5") (pin "3") (pinfunction "EMIT_3") (pintype "passive"))
      (node (ref "OC6") (pin "3") (pinfunction "EMIT_3") (pintype "passive"))
      (node (ref "OC7") (pin "3") (pinfunction "EMIT_3") (pintype "passive"))
      (node (ref "OC8") (pin "3") (pinfunction "EMIT_3") (pintype "passive"))
      (node (ref "OC9") (pin "3") (pinfunction "EMIT_3") (pintype "passive"))
      (node (ref "PI-BESLEME") (pin "4") (pinfunction "4_4") (pintype "bidirectional"))
      (node (ref "PI-BESLEME") (pin "SG1") (pinfunction "GND_SG1") (pintype "passive"))
      (node (ref "PI-BESLEME") (pin "SG2") (pinfunction "GND_SG2") (pintype "passive"))
      (node (ref "PI-HABERLEŞME") (pin "4") (pinfunction "4_4") (pintype "bidirectional"))
      (node (ref "PI-HABERLEŞME") (pin "SG1") (pinfunction "GND_SG1") (pintype "passive"))
      (node (ref "PI-HABERLEŞME") (pin "SG2") (pinfunction "GND_SG2") (pintype "passive"))
      (node (ref "SERVO-ÇIKIŞ") (pin "2") (pinfunction "1_2") (pintype "passive"))
      (node (ref "TP1") (pin "TP") (pinfunction "TP_TP") (pintype "input"))
      (node (ref "U$3") (pin "14") (pinfunction "P14_14") (pintype "bidirectional"))
      (node (ref "U$3") (pin "20") (pinfunction "P20_20") (pintype "bidirectional"))
      (node (ref "U$3") (pin "25") (pinfunction "P25_25") (pintype "bidirectional"))
      (node (ref "U$3") (pin "30") (pinfunction "P30_30") (pintype "bidirectional"))
      (node (ref "U$3") (pin "34") (pinfunction "P34_34") (pintype "bidirectional"))
      (node (ref "U$3") (pin "39") (pinfunction "P39_39") (pintype "bidirectional"))
      (node (ref "U$3") (pin "6") (pinfunction "P6_6") (pintype "bidirectional"))
      (node (ref "U$3") (pin "9") (pinfunction "P9_9") (pintype "bidirectional"))
      (node (ref "U$3") (pin "P$1") (pinfunction "HOLES_P$1") (pintype "bidirectional"))
      (node (ref "U$3") (pin "P$2") (pinfunction "HOLES_P$2") (pintype "bidirectional"))
      (node (ref "U$3") (pin "P$3") (pinfunction "HOLES_P$3") (pintype "bidirectional"))
      (node (ref "U$3") (pin "P$4") (pinfunction "HOLES_P$4") (pintype "bidirectional"))
      (node (ref "U1") (pin "1") (pinfunction "GND_1") (pintype "bidirectional"))
      (node (ref "U2") (pin "4") (pinfunction "GND_4") (pintype "power_in"))
      (node (ref "U4") (pin "21") (pinfunction "GND2_21") (pintype "power_in"))
      (node (ref "U4") (pin "3") (pinfunction "GND_3") (pintype "power_in"))
      (node (ref "U4") (pin "5") (pinfunction "GND1_5") (pintype "power_in"))
      (node (ref "YEDEK_BUTON") (pin "2") (pinfunction "1_2") (pintype "passive"))
    )
    (net (code "23") (name "MCU_N") (class "Default")
      (node (ref "PI-HABERLEŞME") (pin "2") (pinfunction "2_2") (pintype "bidirectional"))
      (node (ref "U1") (pin "6") (pinfunction "D-_6") (pintype "bidirectional"))
    )
    (net (code "24") (name "MCU_P") (class "Default")
      (node (ref "PI-HABERLEŞME") (pin "3") (pinfunction "3_3") (pintype "bidirectional"))
      (node (ref "U1") (pin "5") (pinfunction "D+_5") (pintype "bidirectional"))
    )
    (net (code "25") (name "MCU_RX") (class "Default")
      (node (ref "SJ1") (pin "2") (pinfunction "2_2") (pintype "passive"))
      (node (ref "SJ3") (pin "2") (pinfunction "2_2") (pintype "passive"))
      (node (ref "U4") (pin "30") (pinfunction "PD0(RXD/PCINT16)_30") (pintype "bidirectional"))
    )
    (net (code "26") (name "MCU_TX") (class "Default")
      (node (ref "SJ2") (pin "1") (pinfunction "1_1") (pintype "passive"))
      (node (ref "SJ4") (pin "1") (pinfunction "1_1") (pintype "passive"))
      (node (ref "U4") (pin "31") (pinfunction "PD1(TXD/PCINT17)_31") (pintype "bidirectional"))
    )
    (net (code "27") (name "MISO") (class "Default")
      (node (ref "ICSP") (pin "3") (pinfunction "S_3") (pintype "passive"))
      (node (ref "U4") (pin "16") (pinfunction "(PCINT4/MISO)PB4_16") (pintype "bidirectional"))
    )
    (net (code "28") (name "MOSI") (class "Default")
      (node (ref "ICSP") (pin "2") (pinfunction "S_2") (pintype "passive"))
      (node (ref "U4") (pin "15") (pinfunction "(PCINT3/OC2A/MOSI)PB3_15") (pintype "bidirectional"))
    )
    (net (code "29") (name "NEOPX_S1") (class "Default")
      (node (ref "R5") (pin "1") (pinfunction "1_1") (pintype "passive"))
      (node (ref "U4") (pin "13") (pinfunction "(PCINT1/OC1A)PB1_13") (pintype "bidirectional"))
    )
    (net (code "30") (name "NEOPX_S2") (class "Default")
      (node (ref "R6") (pin "1") (pinfunction "1_1") (pintype "passive"))
      (node (ref "U4") (pin "14") (pinfunction "(PCINT2/SS/OC1B)PB2_14") (pintype "bidirectional"))
    )
    (net (code "31") (name "NEOPX_S3") (class "Default")
      (node (ref "R7") (pin "1") (pinfunction "1_1") (pintype "passive"))
      (node (ref "U$3") (pin "12") (pinfunction "P12_12") (pintype "bidirectional"))
    )
    (net (code "32") (name "Net-(5V-PadA)") (class "Default")
      (node (ref "5V") (pin "A") (pinfunction "A_A") (pintype "passive"))
      (node (ref "R26") (pin "1") (pinfunction "1_1") (pintype "passive"))
    )
    (net (code "33") (name "Net-(12V-PadA)") (class "Default")
      (node (ref "12V") (pin "A") (pinfunction "A_A") (pintype "passive"))
      (node (ref "R27") (pin "1") (pinfunction "1_1") (pintype "passive"))
    )
    (net (code "34") (name "Net-(BLINK-PadA)") (class "Default")
      (node (ref "BLINK") (pin "A") (pinfunction "A_A") (pintype "passive"))
      (node (ref "R1") (pin "1") (pinfunction "1_1") (pintype "passive"))
    )
    (net (code "35") (name "Net-(BOZUK_PARAC-1)") (class "Default")
      (node (ref "BOZUK_PARA") (pin "3") (pinfunction "1_3") (pintype "passive"))
      (node (ref "L8") (pin "C") (pinfunction "C_C") (pintype "passive"))
    )
    (net (code "36") (name "Net-(BT1-+)") (class "Default")
      (node (ref "BT1") (pin "1") (pinfunction "+_1") (pintype "passive"))
      (node (ref "U2") (pin "3") (pinfunction "VBAT_3") (pintype "power_in"))
    )
    (net (code "37") (name "Net-(BUTONB-1)") (class "Default")
      (node (ref "BUTON") (pin "2") (pinfunction "1_2") (pintype "passive"))
      (node (ref "L1") (pin "C") (pinfunction "C_C") (pintype "passive"))
    )
    (net (code "38") (name "Net-(BUTONC-1)") (class "Default")
      (node (ref "BUTON") (pin "3") (pinfunction "1_3") (pintype "passive"))
      (node (ref "L2") (pin "C") (pinfunction "C_C") (pintype "passive"))
    )
    (net (code "39") (name "Net-(BUTOND-1)") (class "Default")
      (node (ref "BUTON") (pin "4") (pinfunction "1_4") (pintype "passive"))
      (node (ref "L3") (pin "C") (pinfunction "C_C") (pintype "passive"))
    )
    (net (code "40") (name "Net-(BUTONE-1)") (class "Default")
      (node (ref "BUTON") (pin "5") (pinfunction "1_5") (pintype "passive"))
      (node (ref "L4") (pin "C") (pinfunction "C_C") (pintype "passive"))
    )
    (net (code "41") (name "Net-(BUTONF-1)") (class "Default")
      (node (ref "BUTON") (pin "6") (pinfunction "1_6") (pintype "passive"))
      (node (ref "L5") (pin "C") (pinfunction "C_C") (pintype "passive"))
    )
    (net (code "42") (name "Net-(BUTONG-1)") (class "Default")
      (node (ref "BUTON") (pin "7") (pinfunction "1_7") (pintype "passive"))
      (node (ref "L6") (pin "C") (pinfunction "C_C") (pintype "passive"))
    )
    (net (code "43") (name "Net-(BUTONH-1)") (class "Default")
      (node (ref "BUTON") (pin "8") (pinfunction "1_8") (pintype "passive"))
      (node (ref "L7") (pin "C") (pinfunction "C_C") (pintype "passive"))
    )
    (net (code "44") (name "Net-(L1-PadA)") (class "Default")
      (node (ref "L1") (pin "A") (pinfunction "A_A") (pintype "passive"))
      (node (ref "R30") (pin "1") (pinfunction "1_1") (pintype "passive"))
    )
    (net (code "45") (name "Net-(L2-PadA)") (class "Default")
      (node (ref "L2") (pin "A") (pinfunction "A_A") (pintype "passive"))
      (node (ref "R32") (pin "1") (pinfunction "1_1") (pintype "passive"))
    )
    (net (code "46") (name "Net-(L3-PadA)") (class "Default")
      (node (ref "L3") (pin "A") (pinfunction "A_A") (pintype "passive"))
      (node (ref "R34") (pin "1") (pinfunction "1_1") (pintype "passive"))
    )
    (net (code "47") (name "Net-(L4-PadA)") (class "Default")
      (node (ref "L4") (pin "A") (pinfunction "A_A") (pintype "passive"))
      (node (ref "R36") (pin "1") (pinfunction "1_1") (pintype "passive"))
    )
    (net (code "48") (name "Net-(L5-PadA)") (class "Default")
      (node (ref "L5") (pin "A") (pinfunction "A_A") (pintype "passive"))
      (node (ref "R38") (pin "1") (pinfunction "1_1") (pintype "passive"))
    )
    (net (code "49") (name "Net-(L6-PadA)") (class "Default")
      (node (ref "L6") (pin "A") (pinfunction "A_A") (pintype "passive"))
      (node (ref "R40") (pin "1") (pinfunction "1_1") (pintype "passive"))
    )
    (net (code "50") (name "Net-(L7-PadA)") (class "Default")
      (node (ref "L7") (pin "A") (pinfunction "A_A") (pintype "passive"))
      (node (ref "R42") (pin "1") (pinfunction "1_1") (pintype "passive"))
    )
    (net (code "51") (name "Net-(L8-PadA)") (class "Default")
      (node (ref "L8") (pin "A") (pinfunction "A_A") (pintype "passive"))
      (node (ref "R44") (pin "1") (pinfunction "1_1") (pintype "passive"))
    )
    (net (code "52") (name "Net-(L9-PadA)") (class "Default")
      (node (ref "L9") (pin "A") (pinfunction "A_A") (pintype "passive"))
      (node (ref "R10") (pin "1") (pinfunction "1_1") (pintype "passive"))
    )
    (net (code "53") (name "Net-(L10-PadA)") (class "Default")
      (node (ref "L10") (pin "A") (pinfunction "A_A") (pintype "passive"))
      (node (ref "R12") (pin "1") (pinfunction "1_1") (pintype "passive"))
    )
    (net (code "54") (name "Net-(NEO-PIXELC-1)") (class "Default")
      (node (ref "NEO-PIXEL") (pin "3") (pinfunction "1_3") (pintype "passive"))
      (node (ref "R5") (pin "2") (pinfunction "2_2") (pintype "passive"))
    )
    (net (code "55") (name "Net-(NEO-PIXELD-1)") (class "Default")
      (node (ref "NEO-PIXEL") (pin "4") (pinfunction "1_4") (pintype "passive"))
      (node (ref "R6") (pin "2") (pinfunction "2_2") (pintype "passive"))
    )
    (net (code "56") (name "Net-(NEO-PIXELE-1)") (class "Default")
      (node (ref "NEO-PIXEL") (pin "5") (pinfunction "1_5") (pintype "passive"))
      (node (ref "R7") (pin "2") (pinfunction "2_2") (pintype "passive"))
    )
    (net (code "57") (name "Net-(OC1-C)") (class "Default")
      (node (ref "C1") (pin "2") (pinfunction "2_2") (pintype "passive"))
      (node (ref "OC1") (pin "2") (pinfunction "C_2") (pintype "passive"))
      (node (ref "R30") (pin "2") (pinfunction "2_2") (pintype "passive"))
      (node (ref "R31") (pin "1") (pinfunction "1_1") (pintype "passive"))
    )
    (net (code "58") (name "Net-(OC2-C)") (class "Default")
      (node (ref "C2") (pin "2") (pinfunction "2_2") (pintype "passive"))
      (node (ref "OC2") (pin "2") (pinfunction "C_2") (pintype "passive"))
      (node (ref "R32") (pin "2") (pinfunction "2_2") (pintype "passive"))
      (node (ref "R33") (pin "1") (pinfunction "1_1") (pintype "passive"))
    )
    (net (code "59") (name "Net-(OC3-C)") (class "Default")
      (node (ref "C3") (pin "2") (pinfunction "2_2") (pintype "passive"))
      (node (ref "OC3") (pin "2") (pinfunction "C_2") (pintype "passive"))
      (node (ref "R34") (pin "2") (pinfunction "2_2") (pintype "passive"))
      (node (ref "R35") (pin "1") (pinfunction "1_1") (pintype "passive"))
    )
    (net (code "60") (name "Net-(OC4-C)") (class "Default")
      (node (ref "C4") (pin "2") (pinfunction "2_2") (pintype "passive"))
      (node (ref "OC4") (pin "2") (pinfunction "C_2") (pintype "passive"))
      (node (ref "R36") (pin "2") (pinfunction "2_2") (pintype "passive"))
      (node (ref "R37") (pin "1") (pinfunction "1_1") (pintype "passive"))
    )
    (net (code "61") (name "Net-(OC5-C)") (class "Default")
      (node (ref "C10") (pin "2") (pinfunction "2_2") (pintype "passive"))
      (node (ref "OC5") (pin "2") (pinfunction "C_2") (pintype "passive"))
      (node (ref "R38") (pin "2") (pinfunction "2_2") (pintype "passive"))
      (node (ref "R39") (pin "1") (pinfunction "1_1") (pintype "passive"))
    )
    (net (code "62") (name "Net-(OC6-C)") (class "Default")
      (node (ref "C11") (pin "2") (pinfunction "2_2") (pintype "passive"))
      (node (ref "OC6") (pin "2") (pinfunction "C_2") (pintype "passive"))
      (node (ref "R40") (pin "2") (pinfunction "2_2") (pintype "passive"))
      (node (ref "R41") (pin "1") (pinfunction "1_1") (pintype "passive"))
    )
    (net (code "63") (name "Net-(OC7-C)") (class "Default")
      (node (ref "C12") (pin "2") (pinfunction "2_2") (pintype "passive"))
      (node (ref "OC7") (pin "2") (pinfunction "C_2") (pintype "passive"))
      (node (ref "R42") (pin "2") (pinfunction "2_2") (pintype "passive"))
      (node (ref "R43") (pin "1") (pinfunction "1_1") (pintype "passive"))
    )
    (net (code "64") (name "Net-(OC8-C)") (class "Default")
      (node (ref "C13") (pin "2") (pinfunction "2_2") (pintype "passive"))
      (node (ref "OC8") (pin "2") (pinfunction "C_2") (pintype "passive"))
      (node (ref "R44") (pin "2") (pinfunction "2_2") (pintype "passive"))
      (node (ref "R45") (pin "1") (pinfunction "1_1") (pintype "passive"))
    )
    (net (code "65") (name "Net-(OC9-C)") (class "Default")
      (node (ref "C21") (pin "2") (pinfunction "2_2") (pintype "passive"))
      (node (ref "OC9") (pin "2") (pinfunction "C_2") (pintype "passive"))
      (node (ref "R10") (pin "2") (pinfunction "2_2") (pintype "passive"))
      (node (ref "R11") (pin "1") (pinfunction "1_1") (pintype "passive"))
    )
    (net (code "66") (name "Net-(OC10-C)") (class "Default")
      (node (ref "C22") (pin "2") (pinfunction "2_2") (pintype "passive"))
      (node (ref "OC10") (pin "2") (pinfunction "C_2") (pintype "passive"))
      (node (ref "R12") (pin "2") (pinfunction "2_2") (pintype "passive"))
      (node (ref "R13") (pin "1") (pinfunction "1_1") (pintype "passive"))
    )
    (net (code "67") (name "Net-(R3-Pad2)") (class "Default")
      (node (ref "R3") (pin "2") (pinfunction "2_2") (pintype "passive"))
      (node (ref "RX") (pin "A") (pinfunction "A_A") (pintype "passive"))
    )
    (net (code "68") (name "Net-(R29-Pad2)") (class "Default")
      (node (ref "R29") (pin "2") (pinfunction "2_2") (pintype "passive"))
      (node (ref "TX") (pin "A") (pinfunction "A_A") (pintype "passive"))
    )
    (net (code "69") (name "Net-(U1-DTR)") (class "Default")
      (node (ref "C8") (pin "1") (pinfunction "1_1") (pintype "passive"))
      (node (ref "U1") (pin "13") (pinfunction "DTR_13") (pintype "bidirectional"))
    )
    (net (code "70") (name "Net-(U1-RX)") (class "Default")
      (node (ref "R54") (pin "1") (pinfunction "1_1") (pintype "passive"))
      (node (ref "U1") (pin "3") (pinfunction "RX_3") (pintype "bidirectional"))
    )
    (net (code "71") (name "Net-(U1-TX)") (class "Default")
      (node (ref "R19") (pin "1") (pinfunction "1_1") (pintype "passive"))
      (node (ref "U1") (pin "2") (pinfunction "TX_2") (pintype "bidirectional"))
    )
    (net (code "72") (name "Net-(U1-V3)") (class "Default")
      (node (ref "C26") (pin "1") (pinfunction "1_1") (pintype "passive"))
      (node (ref "U1") (pin "4") (pinfunction "V3_4") (pintype "bidirectional"))
    )
    (net (code "73") (name "Net-(U1-XI)") (class "Default")
      (node (ref "C24") (pin "1") (pinfunction "1_1") (pintype "passive"))
      (node (ref "U1") (pin "7") (pinfunction "XI_7") (pintype "bidirectional"))
      (node (ref "X1_5032") (pin "P$1") (pinfunction "P$1_P$1") (pintype "bidirectional"))
    )
    (net (code "74") (name "Net-(U1-XO)") (class "Default")
      (node (ref "C25") (pin "1") (pinfunction "1_1") (pintype "passive"))
      (node (ref "U1") (pin "8") (pinfunction "XO_8") (pintype "bidirectional"))
      (node (ref "X1_5032") (pin "P$2") (pinfunction "P$2_P$2") (pintype "bidirectional"))
    )
    (net (code "75") (name "Net-(U2-X1)") (class "Default")
      (node (ref "U2") (pin "1") (pinfunction "X1_1") (pintype "passive"))
      (node (ref "Y1") (pin "2") (pinfunction "2_2") (pintype "passive"))
    )
    (net (code "76") (name "Net-(U2-X2)") (class "Default")
      (node (ref "U2") (pin "2") (pinfunction "X2_2") (pintype "passive"))
      (node (ref "Y1") (pin "1") (pinfunction "1_1") (pintype "passive"))
    )
    (net (code "77") (name "Net-(U4-(PCINT6{slash}XTAL1{slash}TOSC1)PB6)") (class "Default")
      (node (ref "C14") (pin "1") (pinfunction "1_1") (pintype "passive"))
      (node (ref "U4") (pin "7") (pinfunction "(PCINT6/XTAL1/TOSC1)PB6_7") (pintype "bidirectional"))
      (node (ref "X2_5032") (pin "P$1") (pinfunction "P$1_P$1") (pintype "bidirectional"))
    )
    (net (code "78") (name "Net-(U4-(PCINT7{slash}XTAL2{slash}TOSC2)PB7)") (class "Default")
      (node (ref "C15") (pin "1") (pinfunction "1_1") (pintype "passive"))
      (node (ref "U4") (pin "8") (pinfunction "(PCINT7/XTAL2/TOSC2)PB7_8") (pintype "bidirectional"))
      (node (ref "X2_5032") (pin "P$2") (pinfunction "P$2_P$2") (pintype "bidirectional"))
    )
    (net (code "79") (name "Net-(U4-AREF)") (class "Default")
      (node (ref "C7") (pin "1") (pinfunction "1_1") (pintype "passive"))
      (node (ref "U4") (pin "20") (pinfunction "AREF_20") (pintype "power_in"))
    )
    (net (code "80") (name "Net-(YEDEK_BUTONC-1)") (class "Default")
      (node (ref "L9") (pin "C") (pinfunction "C_C") (pintype "passive"))
      (node (ref "YEDEK_BUTON") (pin "3") (pinfunction "1_3") (pintype "passive"))
    )
    (net (code "81") (name "Net-(YEDEK_BUTOND-1)") (class "Default")
      (node (ref "L10") (pin "C") (pinfunction "C_C") (pintype "passive"))
      (node (ref "YEDEK_BUTON") (pin "4") (pinfunction "1_4") (pintype "passive"))
    )
    (net (code "82") (name "PI_RX") (class "Default")
      (node (ref "SJ4") (pin "2") (pinfunction "2_2") (pintype "passive"))
      (node (ref "U$3") (pin "10") (pinfunction "P10_10") (pintype "bidirectional"))
    )
    (net (code "83") (name "PI_TX") (class "Default")
      (node (ref "SJ3") (pin "1") (pinfunction "1_1") (pintype "passive"))
      (node (ref "U$3") (pin "8") (pinfunction "P8_8") (pintype "bidirectional"))
    )
    (net (code "84") (name "RESET") (class "Default")
      (node (ref "C8") (pin "2") (pinfunction "2_2") (pintype "passive"))
      (node (ref "ICSP") (pin "5") (pinfunction "S_5") (pintype "passive"))
      (node (ref "R4") (pin "1") (pinfunction "1_1") (pintype "passive"))
      (node (ref "U4") (pin "29") (pinfunction "(RESET/PCINT14)PC6_29") (pintype "bidirectional"))
    )
    (net (code "85") (name "SCK") (class "Default")
      (node (ref "ICSP") (pin "4") (pinfunction "S_4") (pintype "passive"))
      (node (ref "U4") (pin "17") (pinfunction "(SCK/PCINT5)PB5_17") (pintype "bidirectional"))
    )
    (net (code "86") (name "SCL") (class "Default")
      (node (ref "R8") (pin "1") (pinfunction "1_1") (pintype "passive"))
      (node (ref "U$3") (pin "5") (pinfunction "P5_5") (pintype "bidirectional"))
      (node (ref "U2") (pin "6") (pinfunction "SCL_6") (pintype "input"))
    )
    (net (code "87") (name "SDA") (class "Default")
      (node (ref "R9") (pin "1") (pinfunction "1_1") (pintype "passive"))
      (node (ref "U$3") (pin "3") (pinfunction "P3_3") (pintype "bidirectional"))
      (node (ref "U2") (pin "5") (pinfunction "SDA_5") (pintype "bidirectional"))
    )
    (net (code "88") (name "SERVO_1P") (class "Default")
      (node (ref "SERVO-ÇIKIŞ") (pin "3") (pinfunction "1_3") (pintype "passive"))
      (node (ref "U4") (pin "23") (pinfunction "(ADC0/PCINT8)PC0_23") (pintype "bidirectional"))
    )
    (net (code "89") (name "SERVO_2P") (class "Default")
      (node (ref "SERVO-ÇIKIŞ") (pin "4") (pinfunction "1_4") (pintype "passive"))
      (node (ref "U4") (pin "24") (pinfunction "(ADC1/PCINT9)PC1_24") (pintype "bidirectional"))
    )
    (net (code "90") (name "SERVO_3P") (class "Default")
      (node (ref "SERVO-ÇIKIŞ") (pin "5") (pinfunction "1_5") (pintype "passive"))
      (node (ref "U4") (pin "25") (pinfunction "(ADC2/PCINT10)PC2_25") (pintype "bidirectional"))
    )
    (net (code "91") (name "SERVO_4P") (class "Default")
      (node (ref "SERVO-ÇIKIŞ") (pin "6") (pinfunction "1_6") (pintype "passive"))
      (node (ref "U4") (pin "26") (pinfunction "(ADC3/PCINT11)PC3_26") (pintype "bidirectional"))
    )
    (net (code "92") (name "SERVO_5P") (class "Default")
      (node (ref "SERVO-ÇIKIŞ") (pin "7") (pinfunction "1_7") (pintype "passive"))
      (node (ref "U4") (pin "27") (pinfunction "(ADC4/SDA/PCINT12)PC4_27") (pintype "bidirectional"))
    )
    (net (code "93") (name "SERVO_6P") (class "Default")
      (node (ref "SERVO-ÇIKIŞ") (pin "8") (pinfunction "1_8") (pintype "passive"))
      (node (ref "U4") (pin "28") (pinfunction "(ADC5/SCL/PCINT13)PC5_28") (pintype "bidirectional"))
    )
    (net (code "94") (name "V_PI") (class "Default")
      (node (ref "C5") (pin "1") (pinfunction "1_1") (pintype "passive"))
      (node (ref "R8") (pin "2") (pinfunction "2_2") (pintype "passive"))
      (node (ref "R9") (pin "2") (pinfunction "2_2") (pintype "passive"))
      (node (ref "U$3") (pin "4") (pinfunction "P4_4") (pintype "bidirectional"))
      (node (ref "U2") (pin "8") (pinfunction "VCC_8") (pintype "power_in"))
    )
    (net (code "95") (name "unconnected-(PI-BESLEME-Pad2)") (class "Default")
      (node (ref "PI-BESLEME") (pin "2") (pinfunction "2_2") (pintype "bidirectional"))
    )
    (net (code "96") (name "unconnected-(PI-BESLEME-Pad3)") (class "Default")
      (node (ref "PI-BESLEME") (pin "3") (pinfunction "3_3") (pintype "bidirectional"))
    )
    (net (code "97") (name "unconnected-(PI-HABERLEŞME-Pad1)") (class "Default")
      (node (ref "PI-HABERLEŞME") (pin "1") (pinfunction "1_1") (pintype "bidirectional"))
    )
    (net (code "98") (name "unconnected-(U$3-P1-Pad1)") (class "Default")
      (node (ref "U$3") (pin "1") (pinfunction "P1_1") (pintype "bidirectional"))
    )
    (net (code "99") (name "unconnected-(U$3-P2-Pad2)") (class "Default")
      (node (ref "U$3") (pin "2") (pinfunction "P2_2") (pintype "bidirectional"))
    )
    (net (code "100") (name "unconnected-(U$3-P13-Pad13)") (class "Default")
      (node (ref "U$3") (pin "13") (pinfunction "P13_13") (pintype "bidirectional"))
    )
    (net (code "101") (name "unconnected-(U$3-P15-Pad15)") (class "Default")
      (node (ref "U$3") (pin "15") (pinfunction "P15_15") (pintype "bidirectional"))
    )
    (net (code "102") (name "unconnected-(U$3-P17-Pad17)") (class "Default")
      (node (ref "U$3") (pin "17") (pinfunction "P17_17") (pintype "bidirectional"))
    )
    (net (code "103") (name "unconnected-(U$3-P19-Pad19)") (class "Default")
      (node (ref "U$3") (pin "19") (pinfunction "P19_19") (pintype "bidirectional"))
    )
    (net (code "104") (name "unconnected-(U$3-P21-Pad21)") (class "Default")
      (node (ref "U$3") (pin "21") (pinfunction "P21_21") (pintype "bidirectional"))
    )
    (net (code "105") (name "unconnected-(U$3-P23-Pad23)") (class "Default")
      (node (ref "U$3") (pin "23") (pinfunction "P23_23") (pintype "bidirectional"))
    )
    (net (code "106") (name "unconnected-(U$3-P27-Pad27)") (class "Default")
      (node (ref "U$3") (pin "27") (pinfunction "P27_27") (pintype "bidirectional"))
    )
    (net (code "107") (name "unconnected-(U$3-P28-Pad28)") (class "Default")
      (node (ref "U$3") (pin "28") (pinfunction "P28_28") (pintype "bidirectional"))
    )
    (net (code "108") (name "unconnected-(U$3-P29-Pad29)") (class "Default")
      (node (ref "U$3") (pin "29") (pinfunction "P29_29") (pintype "bidirectional"))
    )
    (net (code "109") (name "unconnected-(U$3-P31-Pad31)") (class "Default")
      (node (ref "U$3") (pin "31") (pinfunction "P31_31") (pintype "bidirectional"))
    )
    (net (code "110") (name "unconnected-(U$3-P33-Pad33)") (class "Default")
      (node (ref "U$3") (pin "33") (pinfunction "P33_33") (pintype "bidirectional"))
    )
    (net (code "111") (name "unconnected-(U$3-P35-Pad35)") (class "Default")
      (node (ref "U$3") (pin "35") (pinfunction "P35_35") (pintype "bidirectional"))
    )
    (net (code "112") (name "unconnected-(U$3-P37-Pad37)") (class "Default")
      (node (ref "U$3") (pin "37") (pinfunction "P37_37") (pintype "bidirectional"))
    )
    (net (code "113") (name "unconnected-(U$3-P40-Pad40)") (class "Default")
      (node (ref "U$3") (pin "40") (pinfunction "P40_40") (pintype "bidirectional"))
    )
    (net (code "114") (name "unconnected-(U1-CTS-Pad9)") (class "Default")
      (node (ref "U1") (pin "9") (pinfunction "CTS_9") (pintype "bidirectional"))
    )
    (net (code "115") (name "unconnected-(U1-DCD-Pad12)") (class "Default")
      (node (ref "U1") (pin "12") (pinfunction "DCD_12") (pintype "bidirectional"))
    )
    (net (code "116") (name "unconnected-(U1-DSR-Pad10)") (class "Default")
      (node (ref "U1") (pin "10") (pinfunction "DSR_10") (pintype "bidirectional"))
    )
    (net (code "117") (name "unconnected-(U1-RI-Pad11)") (class "Default")
      (node (ref "U1") (pin "11") (pinfunction "RI_11") (pintype "bidirectional"))
    )
    (net (code "118") (name "unconnected-(U1-RS232-Pad15)") (class "Default")
      (node (ref "U1") (pin "15") (pinfunction "RS232_15") (pintype "bidirectional"))
    )
    (net (code "119") (name "unconnected-(U1-RTS-Pad14)") (class "Default")
      (node (ref "U1") (pin "14") (pinfunction "RTS_14") (pintype "bidirectional"))
    )
    (net (code "120") (name "unconnected-(U2-SQW{slash}OUT-Pad7)") (class "Default")
      (node (ref "U2") (pin "7") (pinfunction "SQW/OUT_7") (pintype "output"))
    )
    (net (code "121") (name "unconnected-(U4-ADC6-Pad19)") (class "Default")
      (node (ref "U4") (pin "19") (pinfunction "ADC6_19") (pintype "input"))
    )
    (net (code "122") (name "unconnected-(U4-ADC7-Pad22)") (class "Default")
      (node (ref "U4") (pin "22") (pinfunction "ADC7_22") (pintype "input"))
    )
  )
)
